# Qwiic_Pressure_Sensor_-_MS5637.net
KiCad netlist of a schematic drawn in EAGLE
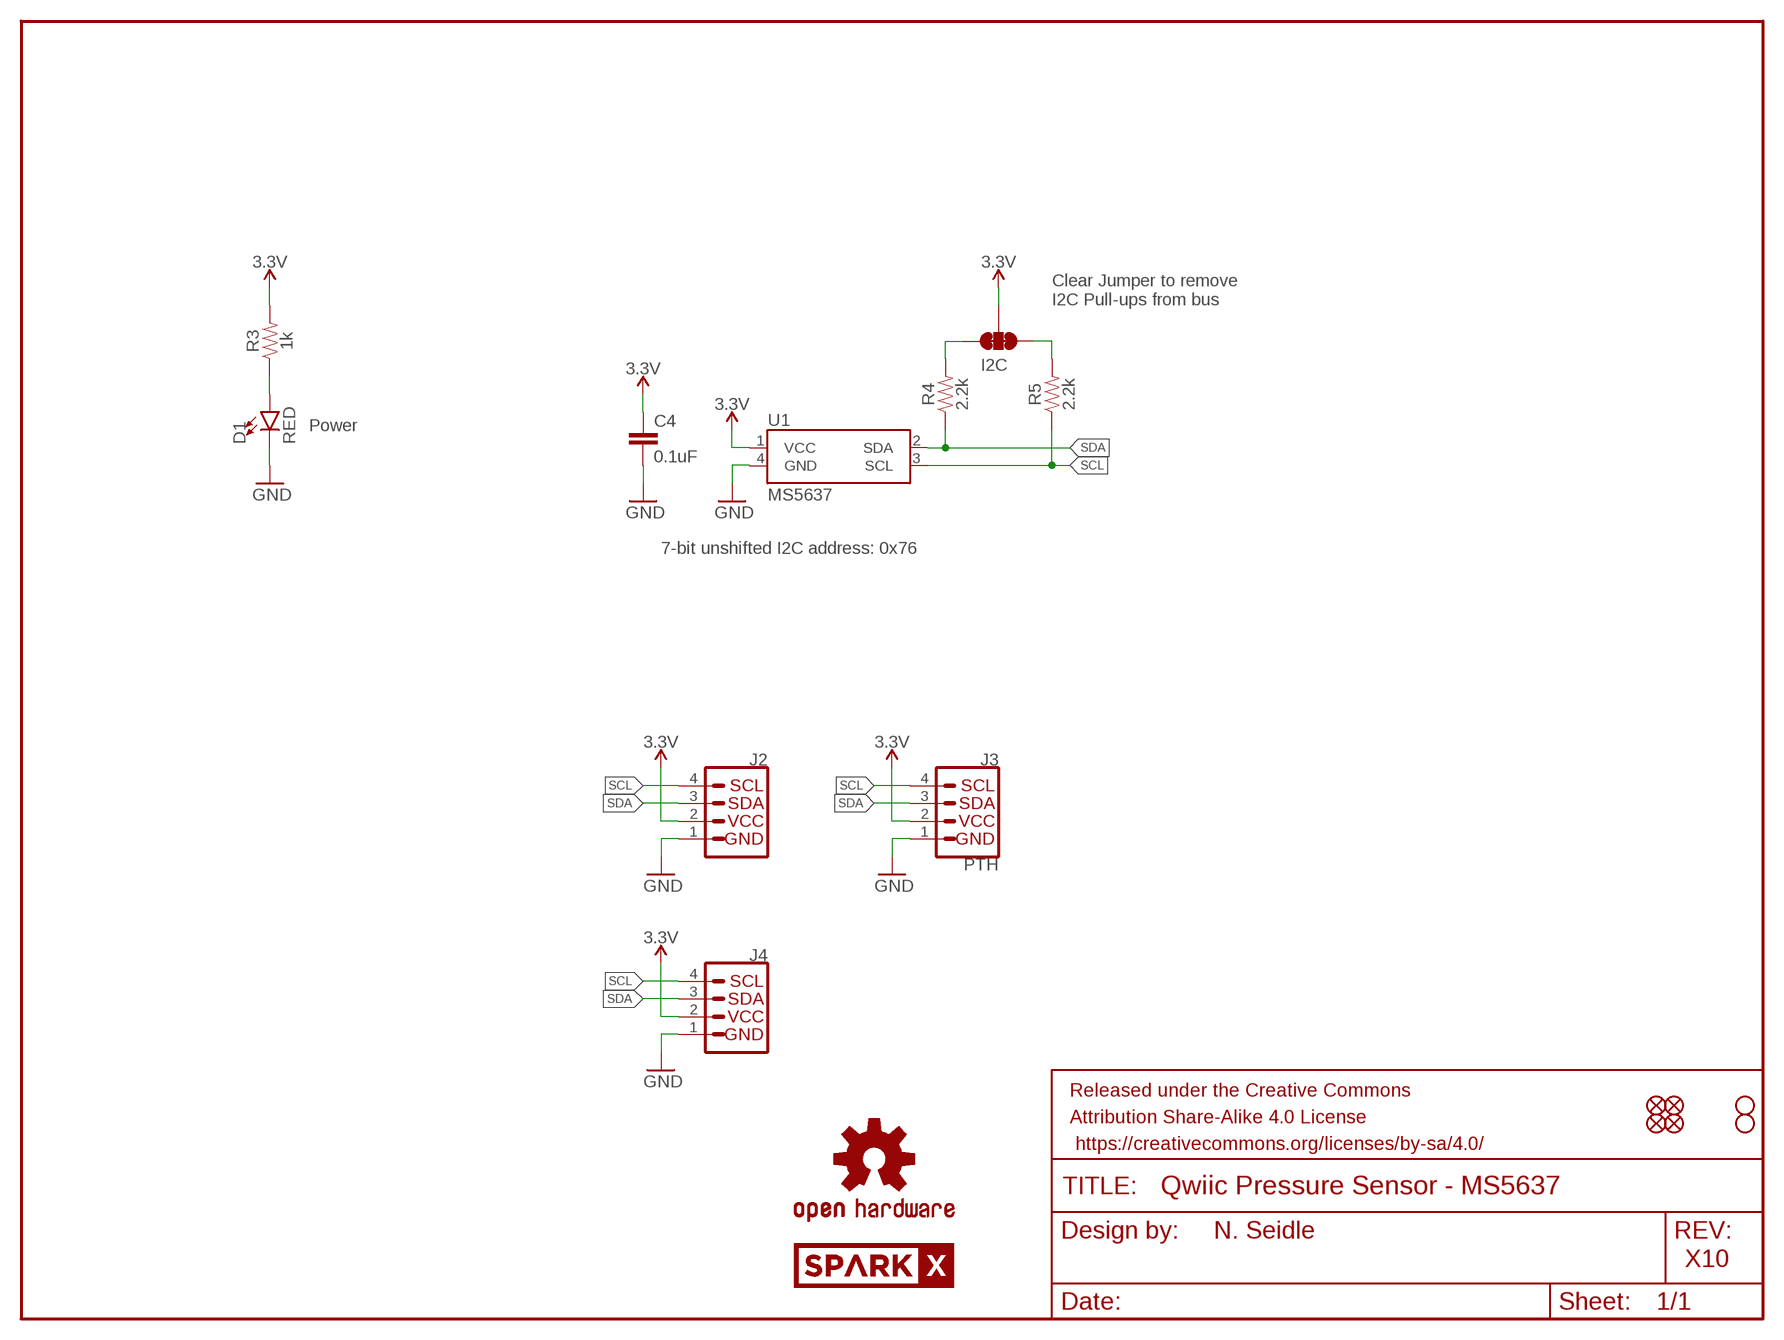
[diagram p0: schematic, sheet 1]

(export (version "E")
  (design (tool "Eeschema 10.0.6"))
  (components
    (comp (ref "C4")
      (value "0.1uF")
      (footprint "eagle-import:0603")
      (libsource (lib "eagle-import") (part "0.1UF-0603-25V-(+80/-20%)"))
    )
    (comp (ref "D1")
      (value "RED")
      (footprint "eagle-import:LED-0603")
      (libsource (lib "eagle-import") (part "LED-RED0603"))
    )
    (comp (ref "FRAME1")
      (value "FRAME-LETTER")
      (footprint "eagle-import:CREATIVE_COMMONS")
      (libsource (lib "eagle-import") (part "FRAME-LETTER"))
    )
    (comp (ref "I2C")
      (value "JUMPER-SMT_3_2-NC_TRACE_SILK")
      (footprint "eagle-import:SMT-JUMPER_3_2-NC_TRACE_SILK")
      (libsource (lib "eagle-import") (part "JUMPER-SMT_3_2-NC_TRACE_SILK"))
    )
    (comp (ref "J2")
      (value "I2C_STANDARDQWIIC")
      (footprint "eagle-import:1X04_1MM_RA")
      (libsource (lib "eagle-import") (part "I2C_STANDARDQWIIC"))
    )
    (comp (ref "J3")
      (value "PTH")
      (footprint "eagle-import:1X04_NO_SILK")
      (libsource (lib "eagle-import") (part "SparkX_I2C_STANDARD_NO_SILK"))
    )
    (comp (ref "J4")
      (value "I2C_STANDARDQWIIC")
      (footprint "eagle-import:1X04_1MM_RA")
      (libsource (lib "eagle-import") (part "I2C_STANDARDQWIIC"))
    )
    (comp (ref "JP1")
      (value "FIDUCIALUFIDUCIAL")
      (footprint "eagle-import:MICRO-FIDUCIAL")
      (libsource (lib "eagle-import") (part "FIDUCIALUFIDUCIAL"))
    )
    (comp (ref "JP2")
      (value "FIDUCIALUFIDUCIAL")
      (footprint "eagle-import:MICRO-FIDUCIAL")
      (libsource (lib "eagle-import") (part "FIDUCIALUFIDUCIAL"))
    )
    (comp (ref "JP3")
      (value "STAND-OFF")
      (footprint "eagle-import:STAND-OFF")
      (libsource (lib "eagle-import") (part "STAND-OFF"))
    )
    (comp (ref "JP4")
      (value "STAND-OFF")
      (footprint "eagle-import:STAND-OFF")
      (libsource (lib "eagle-import") (part "STAND-OFF"))
    )
    (comp (ref "JP5")
      (value "FIDUCIALUFIDUCIAL")
      (footprint "eagle-import:MICRO-FIDUCIAL")
      (libsource (lib "eagle-import") (part "FIDUCIALUFIDUCIAL"))
    )
    (comp (ref "JP6")
      (value "FIDUCIALUFIDUCIAL")
      (footprint "eagle-import:MICRO-FIDUCIAL")
      (libsource (lib "eagle-import") (part "FIDUCIALUFIDUCIAL"))
    )
    (comp (ref "LOGO1")
      (value "OSHW-LOGOMINI")
      (footprint "eagle-import:OSHW-LOGO-MINI")
      (libsource (lib "eagle-import") (part "OSHW-LOGOMINI"))
    )
    (comp (ref "R3")
      (value "1k")
      (footprint "eagle-import:0603")
      (libsource (lib "eagle-import") (part "1KOHM-0603-1/10W-1%"))
    )
    (comp (ref "R4")
      (value "2.2k")
      (footprint "eagle-import:0603")
      (libsource (lib "eagle-import") (part "2.2KOHM-0603-1/10W-1%"))
    )
    (comp (ref "R5")
      (value "2.2k")
      (footprint "eagle-import:0603")
      (libsource (lib "eagle-import") (part "2.2KOHM-0603-1/10W-1%"))
    )
    (comp (ref "U$1")
      (value "SPARKX-LOGO4")
      (footprint "eagle-import:SPARKX-MEDIUM")
      (libsource (lib "eagle-import") (part "SPARKX-LOGO4"))
    )
    (comp (ref "U$2")
      (value "SPARKX-LOGO4")
      (footprint "eagle-import:SPARKX-MEDIUM")
      (libsource (lib "eagle-import") (part "SPARKX-LOGO4"))
    )
    (comp (ref "U1")
      (value "MS5637")
      (footprint "eagle-import:MS5637")
      (libsource (lib "eagle-import") (part "MS5637"))
    )
  )
  (nets
    (net (code "1") (name "3.3V") (class "Default")
      (node (ref "C4") (pin "1") (pinfunction "1_1") (pintype "passive"))
      (node (ref "I2C") (pin "2") (pinfunction "2_2") (pintype "passive"))
      (node (ref "J2") (pin "2") (pinfunction "2_2") (pintype "power_in"))
      (node (ref "J3") (pin "2") (pinfunction "VCC_2") (pintype "power_in"))
      (node (ref "J4") (pin "2") (pinfunction "2_2") (pintype "power_in"))
      (node (ref "R3") (pin "2") (pinfunction "2_2") (pintype "passive"))
      (node (ref "U1") (pin "1") (pinfunction "VCC_1") (pintype "bidirectional"))
    )
    (net (code "2") (name "GND") (class "Default")
      (node (ref "C4") (pin "2") (pinfunction "2_2") (pintype "passive"))
      (node (ref "D1") (pin "C") (pinfunction "C_C") (pintype "passive"))
      (node (ref "J2") (pin "1") (pinfunction "1_1") (pintype "power_in"))
      (node (ref "J3") (pin "1") (pinfunction "GND_1") (pintype "power_in"))
      (node (ref "J4") (pin "1") (pinfunction "1_1") (pintype "power_in"))
      (node (ref "U1") (pin "4") (pinfunction "GND_4") (pintype "bidirectional"))
    )
    (net (code "3") (name "Net-(D1-PadA)") (class "Default")
      (node (ref "D1") (pin "A") (pinfunction "A_A") (pintype "passive"))
      (node (ref "R3") (pin "1") (pinfunction "1_1") (pintype "passive"))
    )
    (net (code "4") (name "Net-(I2C-Pad1)") (class "Default")
      (node (ref "I2C") (pin "1") (pinfunction "1_1") (pintype "passive"))
      (node (ref "R5") (pin "2") (pinfunction "2_2") (pintype "passive"))
    )
    (net (code "5") (name "Net-(I2C-Pad3)") (class "Default")
      (node (ref "I2C") (pin "3") (pinfunction "3_3") (pintype "passive"))
      (node (ref "R4") (pin "2") (pinfunction "2_2") (pintype "passive"))
    )
    (net (code "6") (name "SCL") (class "Default")
      (node (ref "J2") (pin "4") (pinfunction "4_4") (pintype "passive"))
      (node (ref "J3") (pin "4") (pinfunction "SCL_4") (pintype "passive"))
      (node (ref "J4") (pin "4") (pinfunction "4_4") (pintype "passive"))
      (node (ref "R5") (pin "1") (pinfunction "1_1") (pintype "passive"))
      (node (ref "U1") (pin "3") (pinfunction "SCL_3") (pintype "bidirectional"))
    )
    (net (code "7") (name "SDA") (class "Default")
      (node (ref "J2") (pin "3") (pinfunction "3_3") (pintype "passive"))
      (node (ref "J3") (pin "3") (pinfunction "SDA_3") (pintype "passive"))
      (node (ref "J4") (pin "3") (pinfunction "3_3") (pintype "passive"))
      (node (ref "R4") (pin "1") (pinfunction "1_1") (pintype "passive"))
      (node (ref "U1") (pin "2") (pinfunction "SDA_2") (pintype "bidirectional"))
    )
  )
)
